# MCU.net
KiCad netlist of a schematic drawn in Altium Designer
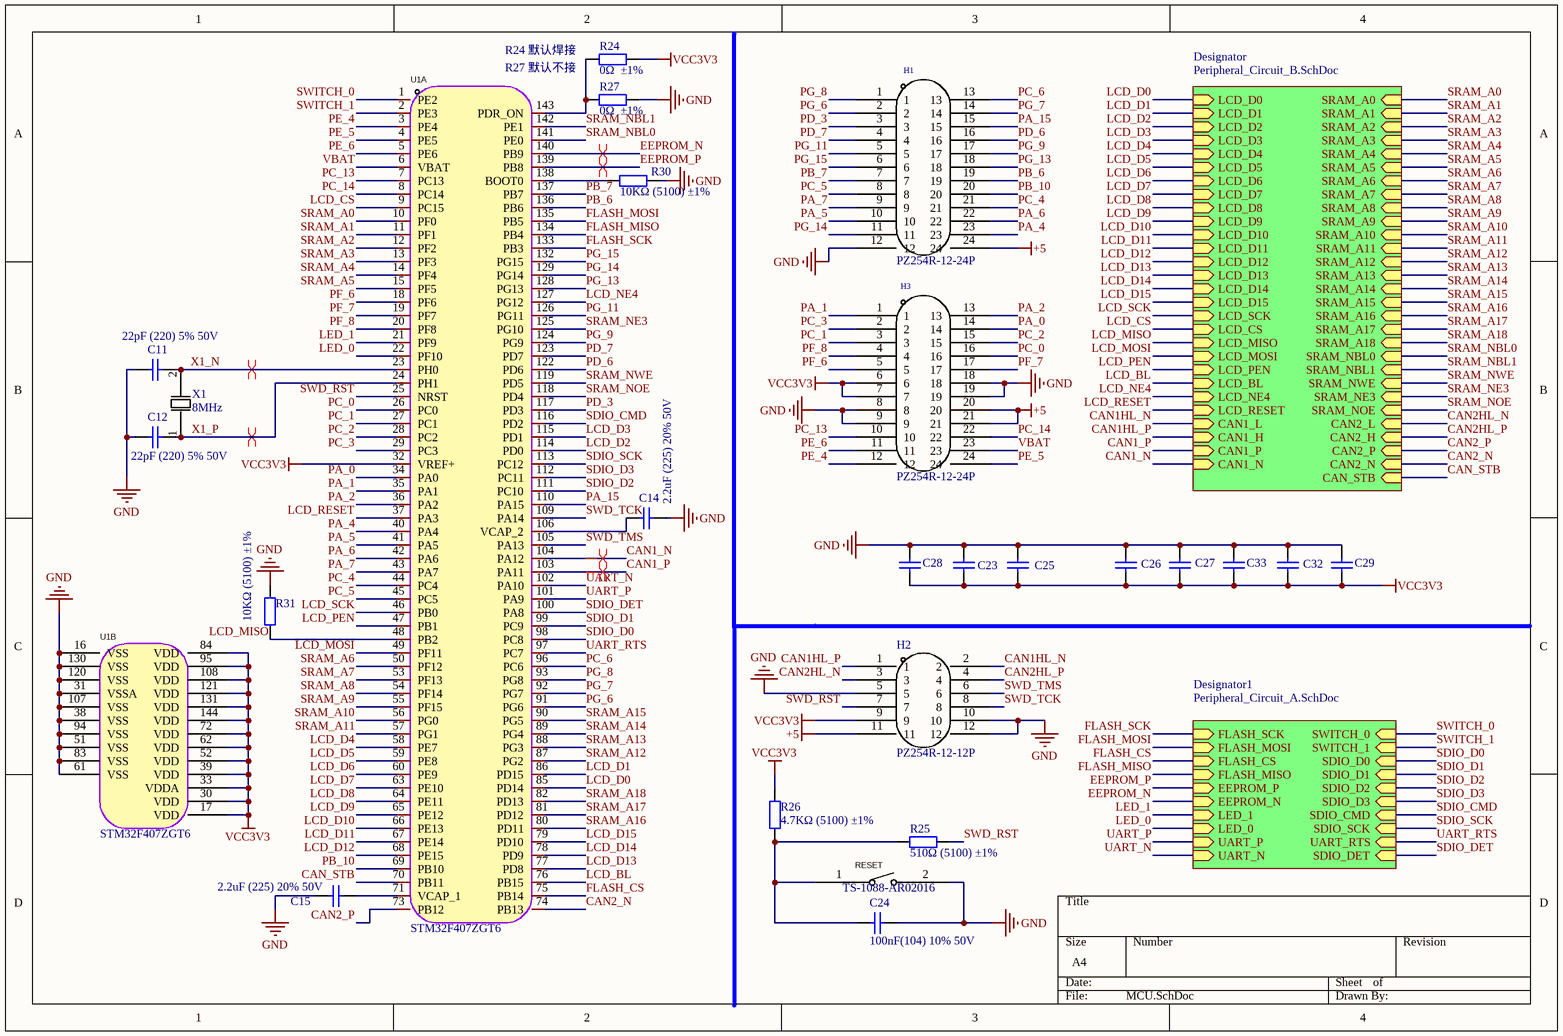
[diagram p0: MCU.SchDoc]

(export (version "E")
  (design (tool "Eeschema 10.0.6"))
  (components
    (comp (ref "C11")
      (value "22pF (220) 5% 50V")
      (footprint "0805_C")
      (description "贴片电容")
      (libsource (lib "Miscellaneous Devices LC") (part "0805 22pF (220) 5% 50V"))
    )
    (comp (ref "C12")
      (value "22pF (220) 5% 50V")
      (footprint "0805_C")
      (description "贴片电容")
      (libsource (lib "Miscellaneous Devices LC") (part "0805 22pF (220) 5% 50V"))
    )
    (comp (ref "C14")
      (value "2.2uF (225) 20% 50V")
      (footprint "0805_C")
      (description "贴片电容")
      (libsource (lib "Miscellaneous Devices LC") (part "0805 2.2uF (225) 20% 50V"))
    )
    (comp (ref "C15")
      (value "2.2uF (225) 20% 50V")
      (footprint "0805_C")
      (description "贴片电容")
      (libsource (lib "Miscellaneous Devices LC") (part "0805 2.2uF (225) 20% 50V"))
    )
    (comp (ref "C23")
      (value "100nF(104) 10% 50V")
      (footprint "0805_C")
      (description "贴片电容")
      (libsource (lib "Miscellaneous Devices LC") (part "0805 100nF(104) 10% 50V"))
    )
    (comp (ref "C24")
      (value "100nF(104) 10% 50V")
      (footprint "0805_C")
      (description "贴片电容")
      (libsource (lib "Miscellaneous Devices LC") (part "0805 100nF(104) 10% 50V"))
    )
    (comp (ref "C25")
      (value "100nF(104) 10% 50V")
      (footprint "0805_C")
      (description "贴片电容")
      (libsource (lib "Miscellaneous Devices LC") (part "0805 100nF(104) 10% 50V"))
    )
    (comp (ref "C26")
      (value "100nF(104) 10% 50V")
      (footprint "0805_C")
      (description "贴片电容")
      (libsource (lib "Miscellaneous Devices LC") (part "0805 100nF(104) 10% 50V"))
    )
    (comp (ref "C27")
      (value "100nF(104) 10% 50V")
      (footprint "0805_C")
      (description "贴片电容")
      (libsource (lib "Miscellaneous Devices LC") (part "0805 100nF(104) 10% 50V"))
    )
    (comp (ref "C28")
      (value "100nF(104) 10% 50V")
      (footprint "0805_C")
      (description "贴片电容")
      (libsource (lib "Miscellaneous Devices LC") (part "0805 100nF(104) 10% 50V"))
    )
    (comp (ref "C29")
      (value "100nF(104) 10% 50V")
      (footprint "0805_C")
      (description "贴片电容")
      (libsource (lib "Miscellaneous Devices LC") (part "0805 100nF(104) 10% 50V"))
    )
    (comp (ref "C32")
      (value "100nF(104) 10% 50V")
      (footprint "0805_C")
      (description "贴片电容")
      (libsource (lib "Miscellaneous Devices LC") (part "0805 100nF(104) 10% 50V"))
    )
    (comp (ref "C33")
      (value "100nF(104) 10% 50V")
      (footprint "0805_C")
      (description "贴片电容")
      (libsource (lib "Miscellaneous Devices LC") (part "0805 100nF(104) 10% 50V"))
    )
    (comp (ref "H1")
      (value "PZ254R-12-24P")
      (footprint "PZ254R-12-24P")
      (description "2X12P 弯针")
      (fields (field (name "MANUFACTURER") "XFCN(兴飞)") (field (name "NAME") "PZ254R-12-24P"))
      (libsource (lib "EXTRA") (part "PZ254R-12-24P"))
    )
    (comp (ref "H2")
      (value "PZ254R-12-12P")
      (footprint "HDR-TH_12P-P2.54-H-M-R2-C6-S2.54")
      (description "2X6P弯针")
      (fields (field (name "MANUFACTURER") "XFCN(兴飞)"))
      (libsource (lib "EXTRA") (part "PZ254R-12-12P"))
    )
    (comp (ref "H3")
      (value "PZ254R-12-24P")
      (footprint "PZ254R-12-24P")
      (description "2X12P 弯针")
      (fields (field (name "MANUFACTURER") "XFCN(兴飞)") (field (name "NAME") "PZ254R-12-24P"))
      (libsource (lib "EXTRA") (part "PZ254R-12-24P"))
    )
    (comp (ref "R24")
      (value "0Ω  ±1%")
      (footprint "0805_R")
      (description "贴片电阻")
      (libsource (lib "Miscellaneous Devices LC") (part "0805 510Ω (5100) 1%"))
    )
    (comp (ref "R25")
      (value "510Ω (5100) ±1%")
      (footprint "0805_R")
      (description "贴片电阻")
      (libsource (lib "Miscellaneous Devices LC") (part "0805 510Ω (5100) 1%"))
    )
    (comp (ref "R26")
      (value "4.7KΩ (5100) ±1%")
      (footprint "0805_R")
      (description "贴片电阻")
      (libsource (lib "") (part "0805 510Ω (5100) 1%_1"))
    )
    (comp (ref "R27")
      (value "0Ω  ±1%")
      (footprint "0805_R")
      (description "贴片电阻")
      (libsource (lib "Miscellaneous Devices LC") (part "0805 510Ω (5100) 1%"))
    )
    (comp (ref "R30")
      (value "10KΩ (5100) ±1%")
      (footprint "0805_R")
      (description "贴片电阻")
      (libsource (lib "") (part "0805 510Ω (5100) 1%_2"))
    )
    (comp (ref "R31")
      (value "10KΩ (5100) ±1%")
      (footprint "0805_R")
      (description "贴片电阻")
      (libsource (lib "") (part "0805 510Ω (5100) 1%_1"))
    )
    (comp (ref "RESET")
      (value "TS-1088-AR02016")
      (footprint "SW-SMD_L3.9-W3.0-P4.45")
      (description "轻触开关")
      (fields (field (name "MANUFACTURER") "XUNPU(讯普)"))
      (libsource (lib "EXTRA") (part "TS-1088-AR02016"))
    )
    (comp (ref "U1")
      (value "STM32F407ZGT6")
      (footprint "LQFP-144_L20.0-W20.0-P0.50-LS22.0-BL")
      (description "STM32F407ZGT6MCU")
      (fields (field (name "MANUFACTURER") "ST(意法半导体)"))
      (libsource (lib "EXTRA") (part "STM32F407ZGT6"))
    )
    (comp (ref "X1")
      (value "8MHZ")
      (footprint "CRYSTAL-SMD_L5.0-W3.2")
      (description "贴片晶振")
      (fields
        (field (name "MANUFACTURER") "YXC(扬兴晶振)")
        (field (name "MANUFACTURER PART") "X50328MSB2GI")
        (field (name "NAME") "8MHz")
      )
      (libsource (lib "EXTRA") (part "X50328MSB2GI"))
    )
  )
  (nets
    (net (code "1") (name "+5") (class "Default")
      (node (ref "H1") (pin "24") (pinfunction "24_24") (pintype "passive"))
      (node (ref "H2") (pin "11") (pinfunction "11_11") (pintype "passive"))
      (node (ref "H3") (pin "20") (pinfunction "20_20") (pintype "passive"))
      (node (ref "H3") (pin "21") (pinfunction "21_21") (pintype "passive"))
    )
    (net (code "2") (name "/CAN1HL_N") (class "Default")
      (node (ref "H2") (pin "2") (pinfunction "2_2") (pintype "passive"))
    )
    (net (code "3") (name "/CAN1HL_P") (class "Default")
      (node (ref "H2") (pin "1") (pinfunction "1_1") (pintype "passive"))
    )
    (net (code "4") (name "/CAN1_N") (class "Default")
      (node (ref "U1") (pin "104") (pinfunction "PA12_104") (pintype "passive"))
    )
    (net (code "5") (name "/CAN1_P") (class "Default")
      (node (ref "U1") (pin "103") (pinfunction "PA11_103") (pintype "passive"))
    )
    (net (code "6") (name "/CAN2HL_N") (class "Default")
      (node (ref "H2") (pin "3") (pinfunction "3_3") (pintype "passive"))
    )
    (net (code "7") (name "/CAN2HL_P") (class "Default")
      (node (ref "H2") (pin "4") (pinfunction "4_4") (pintype "passive"))
    )
    (net (code "8") (name "/CAN2_N") (class "Default")
      (node (ref "U1") (pin "74") (pinfunction "PB13_74") (pintype "passive"))
    )
    (net (code "9") (name "/CAN2_P") (class "Default")
      (node (ref "U1") (pin "73") (pinfunction "PB12_73") (pintype "passive"))
    )
    (net (code "10") (name "/CAN_STB") (class "Default")
      (node (ref "U1") (pin "70") (pinfunction "PB11_70") (pintype "passive"))
    )
    (net (code "11") (name "/EEPROM_N") (class "Default")
      (node (ref "U1") (pin "140") (pinfunction "PB9_140") (pintype "passive"))
    )
    (net (code "12") (name "/EEPROM_P") (class "Default")
      (node (ref "U1") (pin "139") (pinfunction "PB8_139") (pintype "passive"))
    )
    (net (code "13") (name "/FLASH_CS") (class "Default")
      (node (ref "U1") (pin "75") (pinfunction "PB14_75") (pintype "passive"))
    )
    (net (code "14") (name "/FLASH_MISO") (class "Default")
      (node (ref "U1") (pin "134") (pinfunction "PB4_134") (pintype "passive"))
    )
    (net (code "15") (name "/FLASH_MOSI") (class "Default")
      (node (ref "U1") (pin "135") (pinfunction "PB5_135") (pintype "passive"))
    )
    (net (code "16") (name "/FLASH_SCK") (class "Default")
      (node (ref "U1") (pin "133") (pinfunction "PB3_133") (pintype "passive"))
    )
    (net (code "17") (name "/LCD_BL") (class "Default")
      (node (ref "U1") (pin "76") (pinfunction "PB15_76") (pintype "passive"))
    )
    (net (code "18") (name "/LCD_CS") (class "Default")
      (node (ref "U1") (pin "9") (pinfunction "PC15_9") (pintype "passive"))
    )
    (net (code "19") (name "/LCD_D0") (class "Default")
      (node (ref "U1") (pin "85") (pinfunction "PD14_85") (pintype "passive"))
    )
    (net (code "20") (name "/LCD_D1") (class "Default")
      (node (ref "U1") (pin "86") (pinfunction "PD15_86") (pintype "passive"))
    )
    (net (code "21") (name "/LCD_D2") (class "Default")
      (node (ref "U1") (pin "114") (pinfunction "PD0_114") (pintype "passive"))
    )
    (net (code "22") (name "/LCD_D3") (class "Default")
      (node (ref "U1") (pin "115") (pinfunction "PD1_115") (pintype "passive"))
    )
    (net (code "23") (name "/LCD_D4") (class "Default")
      (node (ref "U1") (pin "58") (pinfunction "PE7_58") (pintype "passive"))
    )
    (net (code "24") (name "/LCD_D5") (class "Default")
      (node (ref "U1") (pin "59") (pinfunction "PE8_59") (pintype "passive"))
    )
    (net (code "25") (name "/LCD_D6") (class "Default")
      (node (ref "U1") (pin "60") (pinfunction "PE9_60") (pintype "passive"))
    )
    (net (code "26") (name "/LCD_D7") (class "Default")
      (node (ref "U1") (pin "63") (pinfunction "PE10_63") (pintype "passive"))
    )
    (net (code "27") (name "/LCD_D8") (class "Default")
      (node (ref "U1") (pin "64") (pinfunction "PE11_64") (pintype "passive"))
    )
    (net (code "28") (name "/LCD_D9") (class "Default")
      (node (ref "U1") (pin "65") (pinfunction "PE12_65") (pintype "passive"))
    )
    (net (code "29") (name "/LCD_D10") (class "Default")
      (node (ref "U1") (pin "66") (pinfunction "PE13_66") (pintype "passive"))
    )
    (net (code "30") (name "/LCD_D11") (class "Default")
      (node (ref "U1") (pin "67") (pinfunction "PE14_67") (pintype "passive"))
    )
    (net (code "31") (name "/LCD_D12") (class "Default")
      (node (ref "U1") (pin "68") (pinfunction "PE15_68") (pintype "passive"))
    )
    (net (code "32") (name "/LCD_D13") (class "Default")
      (node (ref "U1") (pin "77") (pinfunction "PD8_77") (pintype "passive"))
    )
    (net (code "33") (name "/LCD_D14") (class "Default")
      (node (ref "U1") (pin "78") (pinfunction "PD9_78") (pintype "passive"))
    )
    (net (code "34") (name "/LCD_D15") (class "Default")
      (node (ref "U1") (pin "79") (pinfunction "PD10_79") (pintype "passive"))
    )
    (net (code "35") (name "/LCD_MISO") (class "Default")
      (node (ref "R31") (pin "2") (pinfunction "2_2") (pintype "passive"))
      (node (ref "U1") (pin "48") (pinfunction "PB2_48") (pintype "passive"))
    )
    (net (code "36") (name "/LCD_MOSI") (class "Default")
      (node (ref "U1") (pin "49") (pinfunction "PF11_49") (pintype "passive"))
    )
    (net (code "37") (name "/LCD_NE4") (class "Default")
      (node (ref "U1") (pin "127") (pinfunction "PG12_127") (pintype "passive"))
    )
    (net (code "38") (name "/LCD_PEN") (class "Default")
      (node (ref "U1") (pin "47") (pinfunction "PB1_47") (pintype "passive"))
    )
    (net (code "39") (name "/LCD_RESET") (class "Default")
      (node (ref "U1") (pin "37") (pinfunction "PA3_37") (pintype "passive"))
    )
    (net (code "40") (name "/LCD_SCK") (class "Default")
      (node (ref "U1") (pin "46") (pinfunction "PB0_46") (pintype "passive"))
    )
    (net (code "41") (name "/LED_0") (class "Default")
      (node (ref "U1") (pin "22") (pinfunction "PF10_22") (pintype "passive"))
    )
    (net (code "42") (name "/LED_1") (class "Default")
      (node (ref "U1") (pin "21") (pinfunction "PF9_21") (pintype "passive"))
    )
    (net (code "43") (name "/PA_0") (class "Default")
      (node (ref "H3") (pin "14") (pinfunction "14_14") (pintype "passive"))
      (node (ref "U1") (pin "34") (pinfunction "PA0_34") (pintype "passive"))
    )
    (net (code "44") (name "/PA_1") (class "Default")
      (node (ref "H3") (pin "1") (pinfunction "1_1") (pintype "passive"))
      (node (ref "U1") (pin "35") (pinfunction "PA1_35") (pintype "passive"))
    )
    (net (code "45") (name "/PA_2") (class "Default")
      (node (ref "H3") (pin "13") (pinfunction "13_13") (pintype "passive"))
      (node (ref "U1") (pin "36") (pinfunction "PA2_36") (pintype "passive"))
    )
    (net (code "46") (name "/PA_4") (class "Default")
      (node (ref "H1") (pin "23") (pinfunction "23_23") (pintype "passive"))
      (node (ref "U1") (pin "40") (pinfunction "PA4_40") (pintype "passive"))
    )
    (net (code "47") (name "/PA_5") (class "Default")
      (node (ref "H1") (pin "10") (pinfunction "10_10") (pintype "passive"))
      (node (ref "U1") (pin "41") (pinfunction "PA5_41") (pintype "passive"))
    )
    (net (code "48") (name "/PA_6") (class "Default")
      (node (ref "H1") (pin "22") (pinfunction "22_22") (pintype "passive"))
      (node (ref "U1") (pin "42") (pinfunction "PA6_42") (pintype "passive"))
    )
    (net (code "49") (name "/PA_7") (class "Default")
      (node (ref "H1") (pin "9") (pinfunction "9_9") (pintype "passive"))
      (node (ref "U1") (pin "43") (pinfunction "PA7_43") (pintype "passive"))
    )
    (net (code "50") (name "/PA_15") (class "Default")
      (node (ref "H1") (pin "15") (pinfunction "15_15") (pintype "passive"))
      (node (ref "U1") (pin "110") (pinfunction "PA15_110") (pintype "passive"))
    )
    (net (code "51") (name "/PB_6") (class "Default")
      (node (ref "H1") (pin "19") (pinfunction "19_19") (pintype "passive"))
      (node (ref "U1") (pin "136") (pinfunction "PB6_136") (pintype "passive"))
    )
    (net (code "52") (name "/PB_7") (class "Default")
      (node (ref "H1") (pin "7") (pinfunction "7_7") (pintype "passive"))
      (node (ref "U1") (pin "137") (pinfunction "PB7_137") (pintype "passive"))
    )
    (net (code "53") (name "/PB_10") (class "Default")
      (node (ref "H1") (pin "20") (pinfunction "20_20") (pintype "passive"))
      (node (ref "U1") (pin "69") (pinfunction "PB10_69") (pintype "passive"))
    )
    (net (code "54") (name "/PC_0") (class "Default")
      (node (ref "H3") (pin "16") (pinfunction "16_16") (pintype "passive"))
      (node (ref "U1") (pin "26") (pinfunction "PC0_26") (pintype "passive"))
    )
    (net (code "55") (name "/PC_1") (class "Default")
      (node (ref "H3") (pin "3") (pinfunction "3_3") (pintype "passive"))
      (node (ref "U1") (pin "27") (pinfunction "PC1_27") (pintype "passive"))
    )
    (net (code "56") (name "/PC_2") (class "Default")
      (node (ref "H3") (pin "15") (pinfunction "15_15") (pintype "passive"))
      (node (ref "U1") (pin "28") (pinfunction "PC2_28") (pintype "passive"))
    )
    (net (code "57") (name "/PC_3") (class "Default")
      (node (ref "H3") (pin "2") (pinfunction "2_2") (pintype "passive"))
      (node (ref "U1") (pin "29") (pinfunction "PC3_29") (pintype "passive"))
    )
    (net (code "58") (name "/PC_4") (class "Default")
      (node (ref "H1") (pin "21") (pinfunction "21_21") (pintype "passive"))
      (node (ref "U1") (pin "44") (pinfunction "PC4_44") (pintype "passive"))
    )
    (net (code "59") (name "/PC_5") (class "Default")
      (node (ref "H1") (pin "8") (pinfunction "8_8") (pintype "passive"))
      (node (ref "U1") (pin "45") (pinfunction "PC5_45") (pintype "passive"))
    )
    (net (code "60") (name "/PC_6") (class "Default")
      (node (ref "H1") (pin "13") (pinfunction "13_13") (pintype "passive"))
      (node (ref "U1") (pin "96") (pinfunction "PC6_96") (pintype "passive"))
    )
    (net (code "61") (name "/PC_13") (class "Default")
      (node (ref "H3") (pin "10") (pinfunction "10_10") (pintype "passive"))
      (node (ref "U1") (pin "7") (pinfunction "PC13_7") (pintype "passive"))
    )
    (net (code "62") (name "/PC_14") (class "Default")
      (node (ref "H3") (pin "22") (pinfunction "22_22") (pintype "passive"))
      (node (ref "U1") (pin "8") (pinfunction "PC14_8") (pintype "passive"))
    )
    (net (code "63") (name "/PD_3") (class "Default")
      (node (ref "H1") (pin "3") (pinfunction "3_3") (pintype "passive"))
      (node (ref "U1") (pin "117") (pinfunction "PD3_117") (pintype "passive"))
    )
    (net (code "64") (name "/PD_6") (class "Default")
      (node (ref "H1") (pin "16") (pinfunction "16_16") (pintype "passive"))
      (node (ref "U1") (pin "122") (pinfunction "PD6_122") (pintype "passive"))
    )
    (net (code "65") (name "/PD_7") (class "Default")
      (node (ref "H1") (pin "4") (pinfunction "4_4") (pintype "passive"))
      (node (ref "U1") (pin "123") (pinfunction "PD7_123") (pintype "passive"))
    )
    (net (code "66") (name "/PE_4") (class "Default")
      (node (ref "H3") (pin "12") (pinfunction "12_12") (pintype "passive"))
      (node (ref "U1") (pin "3") (pinfunction "PE4_3") (pintype "passive"))
    )
    (net (code "67") (name "/PE_5") (class "Default")
      (node (ref "H3") (pin "24") (pinfunction "24_24") (pintype "passive"))
      (node (ref "U1") (pin "4") (pinfunction "PE5_4") (pintype "passive"))
    )
    (net (code "68") (name "/PE_6") (class "Default")
      (node (ref "H3") (pin "11") (pinfunction "11_11") (pintype "passive"))
      (node (ref "U1") (pin "5") (pinfunction "PE6_5") (pintype "passive"))
    )
    (net (code "69") (name "/PF_6") (class "Default")
      (node (ref "H3") (pin "5") (pinfunction "5_5") (pintype "passive"))
      (node (ref "U1") (pin "18") (pinfunction "PF6_18") (pintype "passive"))
    )
    (net (code "70") (name "/PF_7") (class "Default")
      (node (ref "H3") (pin "17") (pinfunction "17_17") (pintype "passive"))
      (node (ref "U1") (pin "19") (pinfunction "PF7_19") (pintype "passive"))
    )
    (net (code "71") (name "/PF_8") (class "Default")
      (node (ref "H3") (pin "4") (pinfunction "4_4") (pintype "passive"))
      (node (ref "U1") (pin "20") (pinfunction "PF8_20") (pintype "passive"))
    )
    (net (code "72") (name "/PG_6") (class "Default")
      (node (ref "H1") (pin "2") (pinfunction "2_2") (pintype "passive"))
      (node (ref "U1") (pin "91") (pinfunction "PG6_91") (pintype "passive"))
    )
    (net (code "73") (name "/PG_7") (class "Default")
      (node (ref "H1") (pin "14") (pinfunction "14_14") (pintype "passive"))
      (node (ref "U1") (pin "92") (pinfunction "PG7_92") (pintype "passive"))
    )
    (net (code "74") (name "/PG_8") (class "Default")
      (node (ref "H1") (pin "1") (pinfunction "1_1") (pintype "passive"))
      (node (ref "U1") (pin "93") (pinfunction "PG8_93") (pintype "passive"))
    )
    (net (code "75") (name "/PG_9") (class "Default")
      (node (ref "H1") (pin "17") (pinfunction "17_17") (pintype "passive"))
      (node (ref "U1") (pin "124") (pinfunction "PG9_124") (pintype "passive"))
    )
    (net (code "76") (name "/PG_11") (class "Default")
      (node (ref "H1") (pin "5") (pinfunction "5_5") (pintype "passive"))
      (node (ref "U1") (pin "126") (pinfunction "PG11_126") (pintype "passive"))
    )
    (net (code "77") (name "/PG_13") (class "Default")
      (node (ref "H1") (pin "18") (pinfunction "18_18") (pintype "passive"))
      (node (ref "U1") (pin "128") (pinfunction "PG13_128") (pintype "passive"))
    )
    (net (code "78") (name "/PG_14") (class "Default")
      (node (ref "H1") (pin "11") (pinfunction "11_11") (pintype "passive"))
      (node (ref "U1") (pin "129") (pinfunction "PG14_129") (pintype "passive"))
    )
    (net (code "79") (name "/PG_15") (class "Default")
      (node (ref "H1") (pin "6") (pinfunction "6_6") (pintype "passive"))
      (node (ref "U1") (pin "132") (pinfunction "PG15_132") (pintype "passive"))
    )
    (net (code "80") (name "/SDIO_CMD") (class "Default")
      (node (ref "U1") (pin "116") (pinfunction "PD2_116") (pintype "passive"))
    )
    (net (code "81") (name "/SDIO_D0") (class "Default")
      (node (ref "U1") (pin "98") (pinfunction "PC8_98") (pintype "passive"))
    )
    (net (code "82") (name "/SDIO_D1") (class "Default")
      (node (ref "U1") (pin "99") (pinfunction "PC9_99") (pintype "passive"))
    )
    (net (code "83") (name "/SDIO_D2") (class "Default")
      (node (ref "U1") (pin "111") (pinfunction "PC10_111") (pintype "passive"))
    )
    (net (code "84") (name "/SDIO_D3") (class "Default")
      (node (ref "U1") (pin "112") (pinfunction "PC11_112") (pintype "passive"))
    )
    (net (code "85") (name "/SDIO_DET") (class "Default")
      (node (ref "U1") (pin "100") (pinfunction "PA8_100") (pintype "passive"))
    )
    (net (code "86") (name "/SDIO_SCK") (class "Default")
      (node (ref "U1") (pin "113") (pinfunction "PC12_113") (pintype "passive"))
    )
    (net (code "87") (name "/SRAM_A0") (class "Default")
      (node (ref "U1") (pin "10") (pinfunction "PF0_10") (pintype "passive"))
    )
    (net (code "88") (name "/SRAM_A1") (class "Default")
      (node (ref "U1") (pin "11") (pinfunction "PF1_11") (pintype "passive"))
    )
    (net (code "89") (name "/SRAM_A2") (class "Default")
      (node (ref "U1") (pin "12") (pinfunction "PF2_12") (pintype "passive"))
    )
    (net (code "90") (name "/SRAM_A3") (class "Default")
      (node (ref "U1") (pin "13") (pinfunction "PF3_13") (pintype "passive"))
    )
    (net (code "91") (name "/SRAM_A4") (class "Default")
      (node (ref "U1") (pin "14") (pinfunction "PF4_14") (pintype "passive"))
    )
    (net (code "92") (name "/SRAM_A5") (class "Default")
      (node (ref "U1") (pin "15") (pinfunction "PF5_15") (pintype "passive"))
    )
    (net (code "93") (name "/SRAM_A6") (class "Default")
      (node (ref "U1") (pin "50") (pinfunction "PF12_50") (pintype "passive"))
    )
    (net (code "94") (name "/SRAM_A7") (class "Default")
      (node (ref "U1") (pin "53") (pinfunction "PF13_53") (pintype "passive"))
    )
    (net (code "95") (name "/SRAM_A8") (class "Default")
      (node (ref "U1") (pin "54") (pinfunction "PF14_54") (pintype "passive"))
    )
    (net (code "96") (name "/SRAM_A9") (class "Default")
      (node (ref "U1") (pin "55") (pinfunction "PF15_55") (pintype "passive"))
    )
    (net (code "97") (name "/SRAM_A10") (class "Default")
      (node (ref "U1") (pin "56") (pinfunction "PG0_56") (pintype "passive"))
    )
    (net (code "98") (name "/SRAM_A11") (class "Default")
      (node (ref "U1") (pin "57") (pinfunction "PG1_57") (pintype "passive"))
    )
    (net (code "99") (name "/SRAM_A12") (class "Default")
      (node (ref "U1") (pin "87") (pinfunction "PG2_87") (pintype "passive"))
    )
    (net (code "100") (name "/SRAM_A13") (class "Default")
      (node (ref "U1") (pin "88") (pinfunction "PG3_88") (pintype "passive"))
    )
    (net (code "101") (name "/SRAM_A14") (class "Default")
      (node (ref "U1") (pin "89") (pinfunction "PG4_89") (pintype "passive"))
    )
    (net (code "102") (name "/SRAM_A15") (class "Default")
      (node (ref "U1") (pin "90") (pinfunction "PG5_90") (pintype "passive"))
    )
    (net (code "103") (name "/SRAM_A16") (class "Default")
      (node (ref "U1") (pin "80") (pinfunction "PD11_80") (pintype "passive"))
    )
    (net (code "104") (name "/SRAM_A17") (class "Default")
      (node (ref "U1") (pin "81") (pinfunction "PD12_81") (pintype "passive"))
    )
    (net (code "105") (name "/SRAM_A18") (class "Default")
      (node (ref "U1") (pin "82") (pinfunction "PD13_82") (pintype "passive"))
    )
    (net (code "106") (name "/SRAM_NBL0") (class "Default")
      (node (ref "U1") (pin "141") (pinfunction "PE0_141") (pintype "passive"))
    )
    (net (code "107") (name "/SRAM_NBL1") (class "Default")
      (node (ref "U1") (pin "142") (pinfunction "PE1_142") (pintype "passive"))
    )
    (net (code "108") (name "/SRAM_NE3") (class "Default")
      (node (ref "U1") (pin "125") (pinfunction "PG10_125") (pintype "passive"))
    )
    (net (code "109") (name "/SRAM_NOE") (class "Default")
      (node (ref "U1") (pin "118") (pinfunction "PD4_118") (pintype "passive"))
    )
    (net (code "110") (name "/SRAM_NWE") (class "Default")
      (node (ref "U1") (pin "119") (pinfunction "PD5_119") (pintype "passive"))
    )
    (net (code "111") (name "/SWD_RST") (class "Default")
      (node (ref "H2") (pin "7") (pinfunction "7_7") (pintype "passive"))
      (node (ref "R25") (pin "2") (pinfunction "2_2") (pintype "passive"))
      (node (ref "U1") (pin "25") (pinfunction "NRST_25") (pintype "passive"))
    )
    (net (code "112") (name "/SWD_TCK") (class "Default")
      (node (ref "H2") (pin "8") (pinfunction "8_8") (pintype "passive"))
      (node (ref "U1") (pin "109") (pinfunction "PA14_109") (pintype "passive"))
    )
    (net (code "113") (name "/SWD_TMS") (class "Default")
      (node (ref "H2") (pin "6") (pinfunction "6_6") (pintype "passive"))
      (node (ref "U1") (pin "105") (pinfunction "PA13_105") (pintype "passive"))
    )
    (net (code "114") (name "/SWITCH_0") (class "Default")
      (node (ref "U1") (pin "1") (pinfunction "PE2_1") (pintype "passive"))
    )
    (net (code "115") (name "/SWITCH_1") (class "Default")
      (node (ref "U1") (pin "2") (pinfunction "PE3_2") (pintype "passive"))
    )
    (net (code "116") (name "/UART_N") (class "Default")
      (node (ref "U1") (pin "102") (pinfunction "PA10_102") (pintype "passive"))
    )
    (net (code "117") (name "/UART_P") (class "Default")
      (node (ref "U1") (pin "101") (pinfunction "PA9_101") (pintype "passive"))
    )
    (net (code "118") (name "/UART_RTS") (class "Default")
      (node (ref "U1") (pin "97") (pinfunction "PC7_97") (pintype "passive"))
    )
    (net (code "119") (name "/VBAT") (class "Default")
      (node (ref "H3") (pin "23") (pinfunction "23_23") (pintype "passive"))
      (node (ref "U1") (pin "6") (pinfunction "VBAT_6") (pintype "passive"))
    )
    (net (code "120") (name "/X1_N") (class "Default")
      (node (ref "C11") (pin "2") (pinfunction "2_2") (pintype "passive"))
      (node (ref "U1") (pin "23") (pinfunction "PH0_23") (pintype "passive"))
      (node (ref "X1") (pin "2") (pinfunction "2_2") (pintype "passive"))
    )
    (net (code "121") (name "/X1_P") (class "Default")
      (node (ref "C12") (pin "2") (pinfunction "2_2") (pintype "passive"))
      (node (ref "U1") (pin "24") (pinfunction "PH1_24") (pintype "passive"))
      (node (ref "X1") (pin "1") (pinfunction "1_1") (pintype "passive"))
    )
    (net (code "122") (name "GND") (class "Default")
      (node (ref "C11") (pin "1") (pinfunction "1_1") (pintype "passive"))
      (node (ref "C12") (pin "1") (pinfunction "1_1") (pintype "passive"))
      (node (ref "C14") (pin "2") (pinfunction "2_2") (pintype "passive"))
      (node (ref "C15") (pin "1") (pinfunction "1_1") (pintype "passive"))
      (node (ref "C23") (pin "2") (pinfunction "2_2") (pintype "passive"))
      (node (ref "C24") (pin "1") (pinfunction "1_1") (pintype "passive"))
      (node (ref "C25") (pin "2") (pinfunction "2_2") (pintype "passive"))
      (node (ref "C26") (pin "2") (pinfunction "2_2") (pintype "passive"))
      (node (ref "C27") (pin "2") (pinfunction "2_2") (pintype "passive"))
      (node (ref "C28") (pin "1") (pinfunction "1_1") (pintype "passive"))
      (node (ref "C29") (pin "1") (pinfunction "1_1") (pintype "passive"))
      (node (ref "C32") (pin "2") (pinfunction "2_2") (pintype "passive"))
      (node (ref "C33") (pin "1") (pinfunction "1_1") (pintype "passive"))
      (node (ref "H1") (pin "12") (pinfunction "12_12") (pintype "passive"))
      (node (ref "H2") (pin "10") (pinfunction "10_10") (pintype "passive"))
      (node (ref "H2") (pin "12") (pinfunction "12_12") (pintype "passive"))
      (node (ref "H2") (pin "5") (pinfunction "5_5") (pintype "passive"))
      (node (ref "H3") (pin "18") (pinfunction "18_18") (pintype "passive"))
      (node (ref "H3") (pin "19") (pinfunction "19_19") (pintype "passive"))
      (node (ref "H3") (pin "8") (pinfunction "8_8") (pintype "passive"))
      (node (ref "H3") (pin "9") (pinfunction "9_9") (pintype "passive"))
      (node (ref "R27") (pin "2") (pinfunction "2_2") (pintype "passive"))
      (node (ref "R30") (pin "1") (pinfunction "1_1") (pintype "passive"))
      (node (ref "R31") (pin "1") (pinfunction "1_1") (pintype "passive"))
      (node (ref "RESET") (pin "2") (pinfunction "2_2") (pintype "passive"))
      (node (ref "U1") (pin "107") (pinfunction "VSS_107") (pintype "passive"))
      (node (ref "U1") (pin "120") (pinfunction "VSS_120") (pintype "passive"))
      (node (ref "U1") (pin "130") (pinfunction "VSS_130") (pintype "passive"))
      (node (ref "U1") (pin "16") (pinfunction "VSS_16") (pintype "passive"))
      (node (ref "U1") (pin "31") (pinfunction "VSSA_31") (pintype "passive"))
      (node (ref "U1") (pin "38") (pinfunction "VSS_38") (pintype "passive"))
      (node (ref "U1") (pin "51") (pinfunction "VSS_51") (pintype "passive"))
      (node (ref "U1") (pin "61") (pinfunction "VSS_61") (pintype "passive"))
      (node (ref "U1") (pin "83") (pinfunction "VSS_83") (pintype "passive"))
      (node (ref "U1") (pin "94") (pinfunction "VSS_94") (pintype "passive"))
    )
    (net (code "123") (name "Net-(C24-Pad2)") (class "Default")
      (node (ref "C24") (pin "2") (pinfunction "2_2") (pintype "passive"))
      (node (ref "R25") (pin "1") (pinfunction "1_1") (pintype "passive"))
      (node (ref "R26") (pin "2") (pinfunction "2_2") (pintype "passive"))
      (node (ref "RESET") (pin "1") (pinfunction "1_1") (pintype "passive"))
    )
    (net (code "124") (name "Net-(U1A-BOOT0)") (class "Default")
      (node (ref "R30") (pin "2") (pinfunction "2_2") (pintype "passive"))
      (node (ref "U1") (pin "138") (pinfunction "BOOT0_138") (pintype "passive"))
    )
    (net (code "125") (name "Net-(U1A-PDR_ON)") (class "Default")
      (node (ref "R24") (pin "1") (pinfunction "1_1") (pintype "passive"))
      (node (ref "R27") (pin "1") (pinfunction "1_1") (pintype "passive"))
      (node (ref "U1") (pin "143") (pinfunction "PDR_ON_143") (pintype "passive"))
    )
    (net (code "126") (name "Net-(U1A-VCAP_1)") (class "Default")
      (node (ref "C15") (pin "2") (pinfunction "2_2") (pintype "passive"))
      (node (ref "U1") (pin "71") (pinfunction "VCAP_1_71") (pintype "passive"))
    )
    (net (code "127") (name "Net-(U1A-VCAP_2)") (class "Default")
      (node (ref "C14") (pin "1") (pinfunction "1_1") (pintype "passive"))
      (node (ref "U1") (pin "106") (pinfunction "VCAP_2_106") (pintype "passive"))
    )
    (net (code "128") (name "VCC3V3") (class "Default")
      (node (ref "C23") (pin "1") (pinfunction "1_1") (pintype "passive"))
      (node (ref "C25") (pin "1") (pinfunction "1_1") (pintype "passive"))
      (node (ref "C26") (pin "1") (pinfunction "1_1") (pintype "passive"))
      (node (ref "C27") (pin "1") (pinfunction "1_1") (pintype "passive"))
      (node (ref "C28") (pin "2") (pinfunction "2_2") (pintype "passive"))
      (node (ref "C29") (pin "2") (pinfunction "2_2") (pintype "passive"))
      (node (ref "C32") (pin "1") (pinfunction "1_1") (pintype "passive"))
      (node (ref "C33") (pin "2") (pinfunction "2_2") (pintype "passive"))
      (node (ref "H2") (pin "9") (pinfunction "9_9") (pintype "passive"))
      (node (ref "H3") (pin "6") (pinfunction "6_6") (pintype "passive"))
      (node (ref "H3") (pin "7") (pinfunction "7_7") (pintype "passive"))
      (node (ref "R24") (pin "2") (pinfunction "2_2") (pintype "passive"))
      (node (ref "R26") (pin "1") (pinfunction "1_1") (pintype "passive"))
      (node (ref "U1") (pin "108") (pinfunction "VDD_108") (pintype "passive"))
      (node (ref "U1") (pin "121") (pinfunction "VDD_121") (pintype "passive"))
      (node (ref "U1") (pin "131") (pinfunction "VDD_131") (pintype "passive"))
      (node (ref "U1") (pin "144") (pinfunction "VDD_144") (pintype "passive"))
      (node (ref "U1") (pin "17") (pinfunction "VDD_17") (pintype "passive"))
      (node (ref "U1") (pin "30") (pinfunction "VDD_30") (pintype "passive"))
      (node (ref "U1") (pin "32") (pinfunction "VREF+_32") (pintype "passive"))
      (node (ref "U1") (pin "33") (pinfunction "VDDA_33") (pintype "passive"))
      (node (ref "U1") (pin "39") (pinfunction "VDD_39") (pintype "passive"))
      (node (ref "U1") (pin "52") (pinfunction "VDD_52") (pintype "passive"))
      (node (ref "U1") (pin "62") (pinfunction "VDD_62") (pintype "passive"))
      (node (ref "U1") (pin "72") (pinfunction "VDD_72") (pintype "passive"))
      (node (ref "U1") (pin "84") (pinfunction "VDD_84") (pintype "passive"))
      (node (ref "U1") (pin "95") (pinfunction "VDD_95") (pintype "passive"))
    )
  )
)
